# CNC-PowerSwitch-2016-v0_95.net
KiCad netlist of a schematic drawn in EAGLE
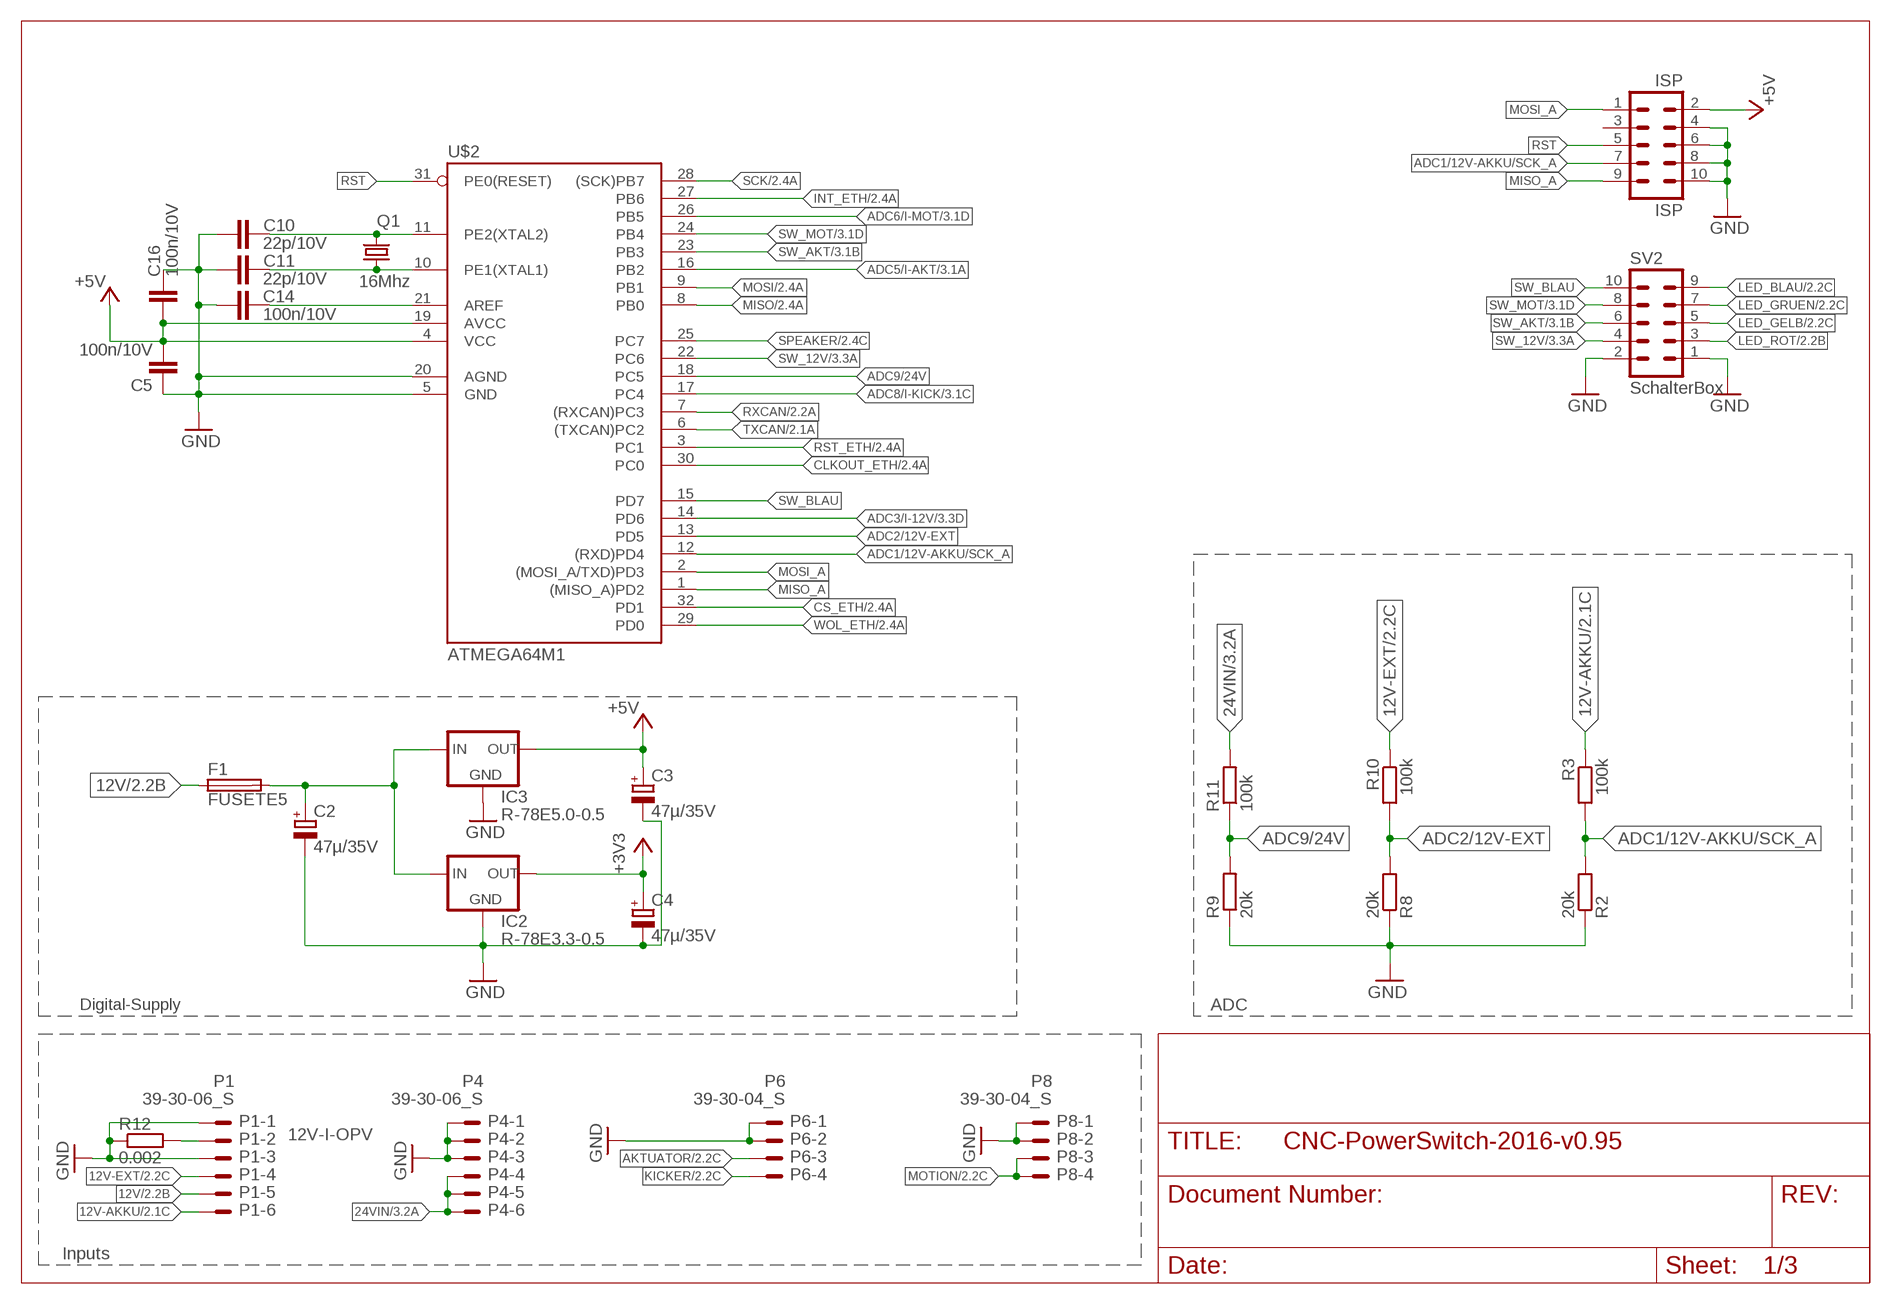
[diagram p0: schematic, sheet 1]
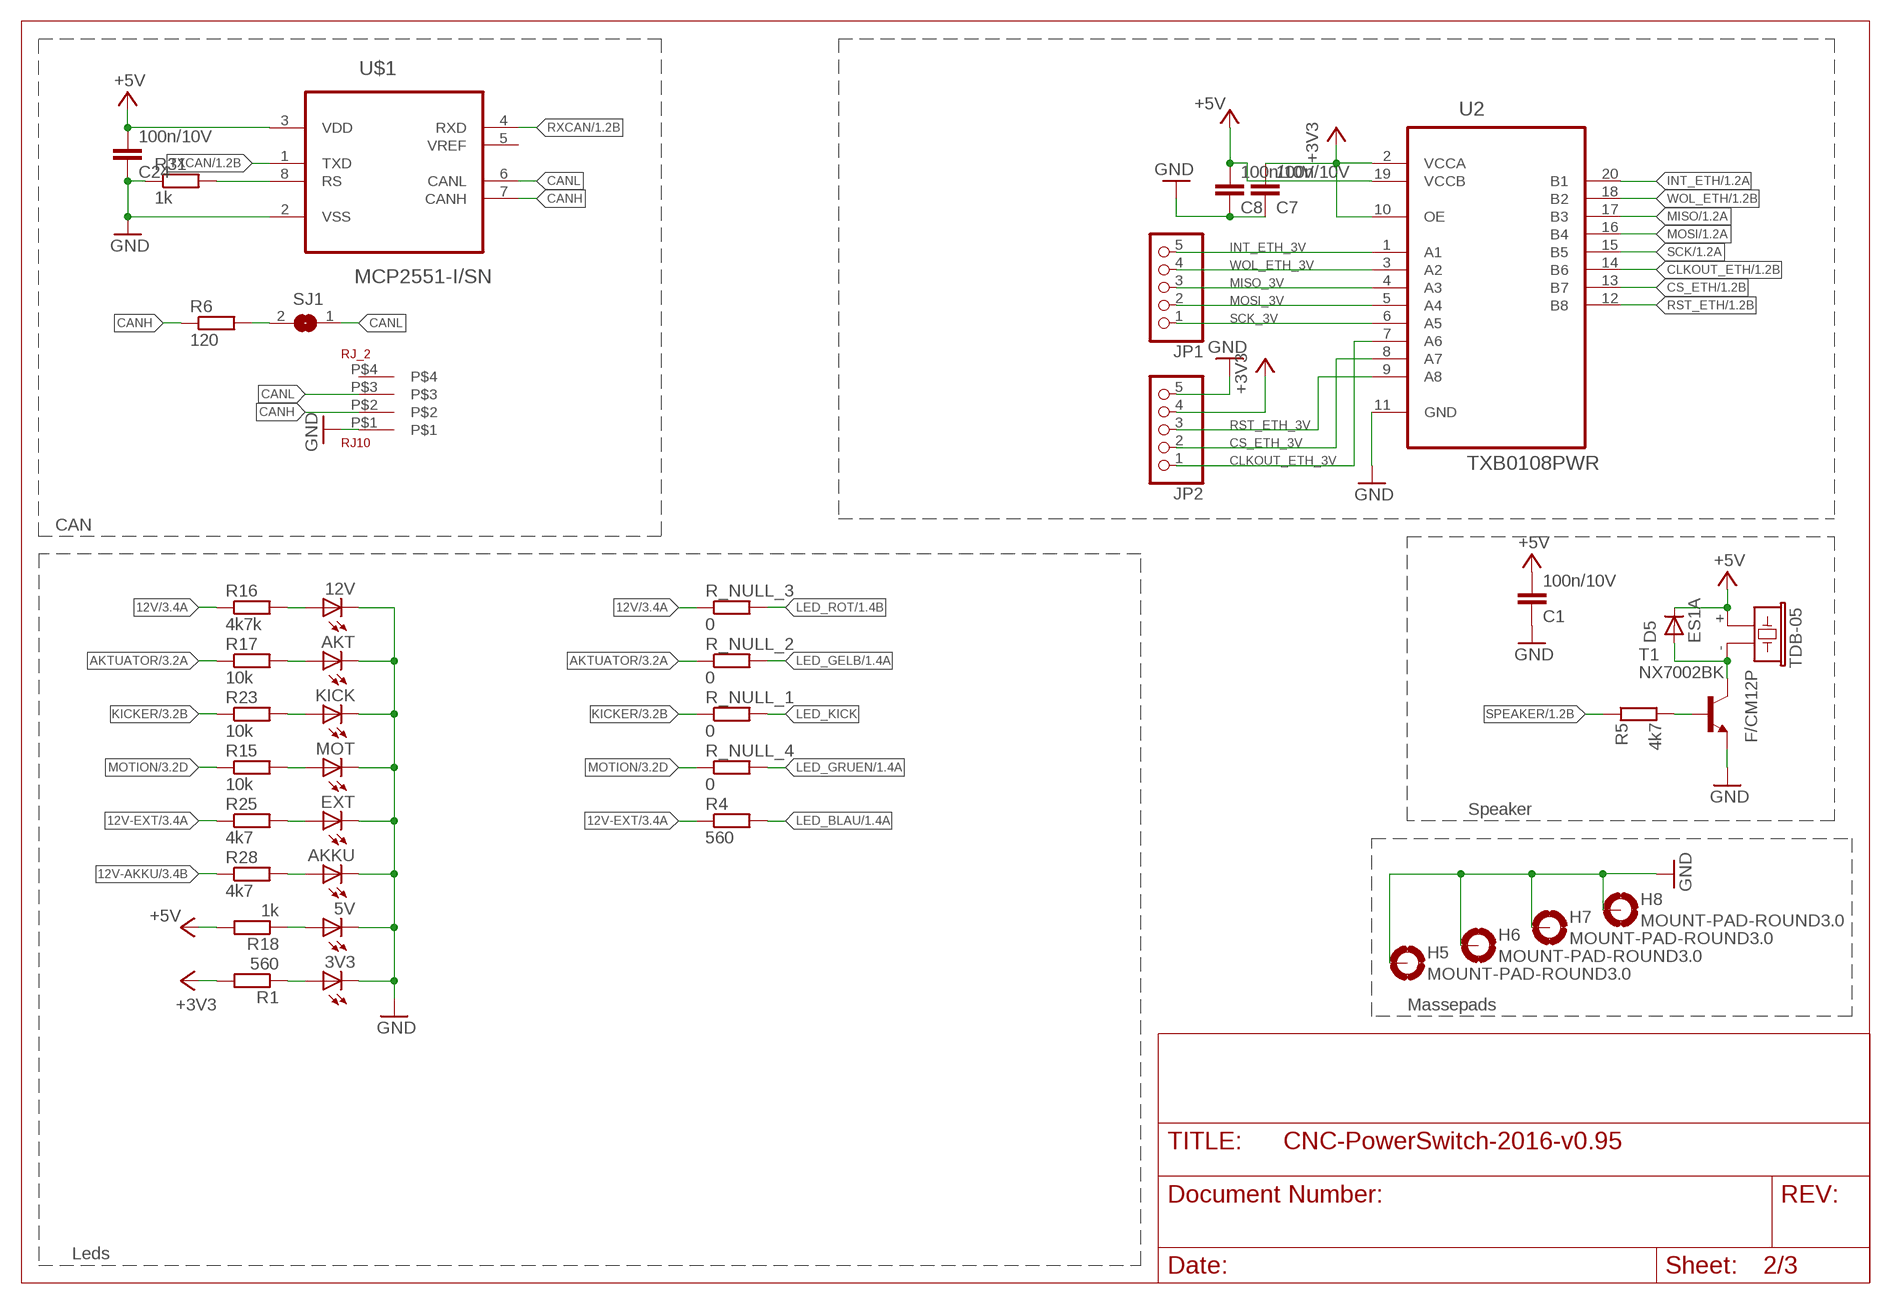
[diagram p1: schematic, sheet 2]
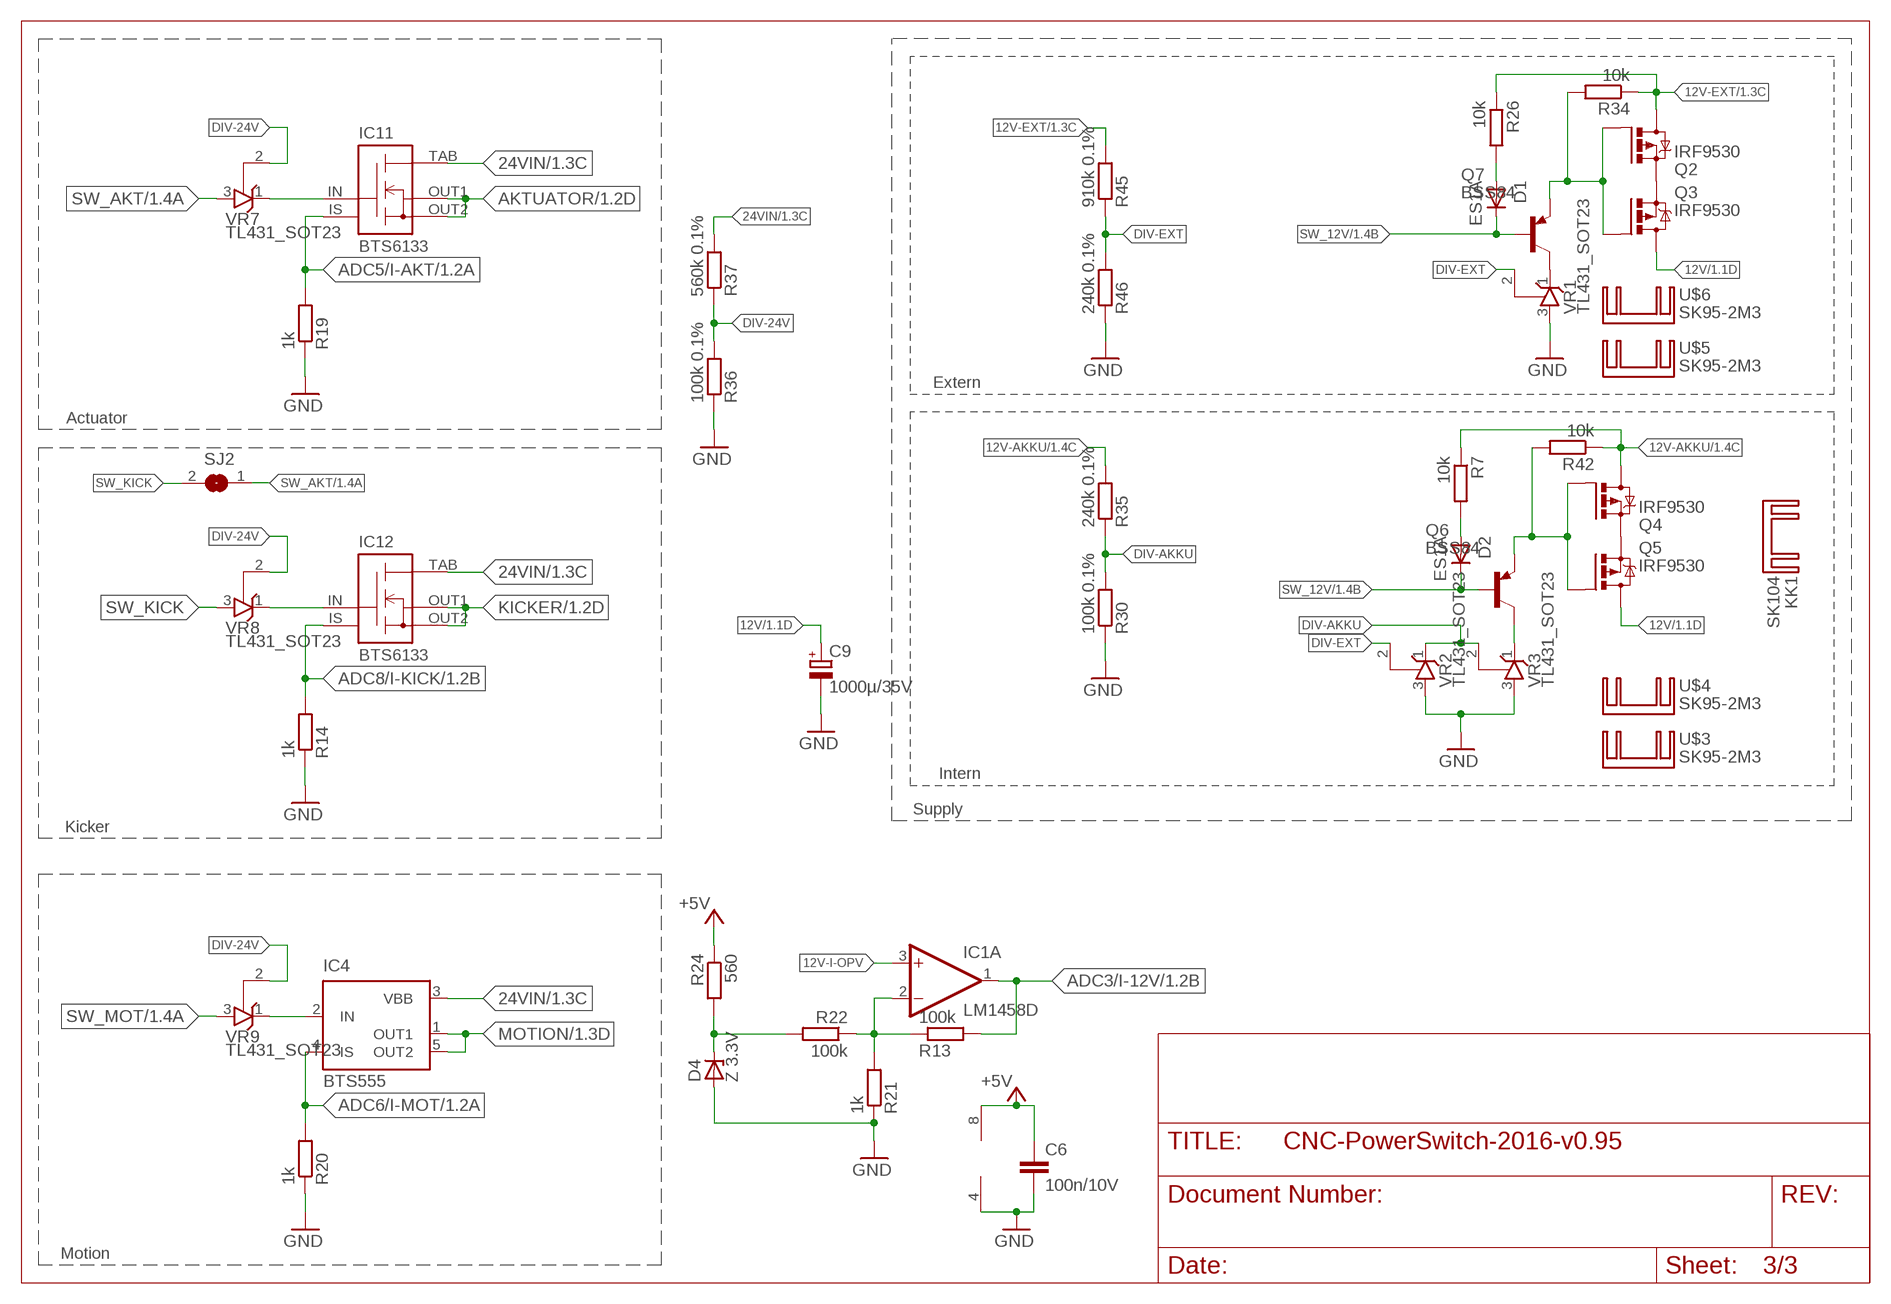
[diagram p2: schematic, sheet 3]

(export (version "E")
  (design (tool "Eeschema 10.0.6"))
  (components
    (comp (ref "C2")
      (value "47µ/35V")
      (footprint "eagle-import:PANASONIC_D")
      (libsource (lib "eagle-import") (part "CPOL-EUD"))
    )
    (comp (ref "C3")
      (value "47µ/35V")
      (footprint "eagle-import:PANASONIC_D")
      (libsource (lib "eagle-import") (part "CPOL-EUD"))
    )
    (comp (ref "C4")
      (value "47µ/35V")
      (footprint "eagle-import:PANASONIC_D")
      (libsource (lib "eagle-import") (part "CPOL-EUD"))
    )
    (comp (ref "C5")
      (value "100n/10V")
      (footprint "eagle-import:C0603")
      (libsource (lib "eagle-import") (part "C-EUC0603"))
    )
    (comp (ref "C10")
      (value "22p/10V")
      (footprint "eagle-import:C0603")
      (libsource (lib "eagle-import") (part "C-EUC0603"))
    )
    (comp (ref "C11")
      (value "22p/10V")
      (footprint "eagle-import:C0603")
      (libsource (lib "eagle-import") (part "C-EUC0603"))
    )
    (comp (ref "C14")
      (value "100n/10V")
      (footprint "eagle-import:C0603")
      (libsource (lib "eagle-import") (part "C-EUC0603"))
    )
    (comp (ref "C16")
      (value "100n/10V")
      (footprint "eagle-import:C0603")
      (libsource (lib "eagle-import") (part "C-EUC0603"))
    )
    (comp (ref "F1")
      (value "FUSETE5")
      (footprint "eagle-import:TE5")
      (libsource (lib "eagle-import") (part "FUSETE5"))
    )
    (comp (ref "IC2")
      (value "R-78E3.3-0.5")
      (footprint "eagle-import:SIP3")
      (fields (field (name "MF") "Recom") (field (name "MPN") "R-783.3-0.5"))
      (libsource (lib "eagle-import") (part "R-78E-0.53.3"))
    )
    (comp (ref "IC3")
      (value "R-78E5.0-0.5")
      (footprint "eagle-import:SIP3")
      (fields (field (name "MF") "Recom") (field (name "MPN") "R-785.0-0.5"))
      (libsource (lib "eagle-import") (part "R-78E-0.55.0"))
    )
    (comp (ref "ISP")
      (value "ISP")
      (footprint "eagle-import:ML10")
      (libsource (lib "eagle-import") (part "ML10"))
    )
    (comp (ref "P1")
      (value "39-30-06_S")
      (footprint "eagle-import:39-30-_06_")
      (libsource (lib "eagle-import") (part "39-30-?06?_S"))
    )
    (comp (ref "P4")
      (value "39-30-06_S")
      (footprint "eagle-import:39-30-_06_")
      (libsource (lib "eagle-import") (part "39-30-?06?_S"))
    )
    (comp (ref "P6")
      (value "39-30-04_S")
      (footprint "eagle-import:39-30-_04_")
      (libsource (lib "eagle-import") (part "39-30-?04?_S"))
    )
    (comp (ref "P8")
      (value "39-30-04_S")
      (footprint "eagle-import:39-30-_04_")
      (libsource (lib "eagle-import") (part "39-30-?04?_S"))
    )
    (comp (ref "Q1")
      (value "16Mhz")
      (footprint "eagle-import:HC49UP")
      (libsource (lib "eagle-import") (part "CRYSTALHC49UP"))
    )
    (comp (ref "R2")
      (value "20k")
      (footprint "eagle-import:R0805")
      (libsource (lib "eagle-import") (part "R-EU_R0805"))
    )
    (comp (ref "R3")
      (value "100k")
      (footprint "eagle-import:R0805")
      (libsource (lib "eagle-import") (part "R-EU_R0805"))
    )
    (comp (ref "R8")
      (value "20k")
      (footprint "eagle-import:R0805")
      (libsource (lib "eagle-import") (part "R-EU_R0805"))
    )
    (comp (ref "R9")
      (value "20k")
      (footprint "eagle-import:R0805")
      (libsource (lib "eagle-import") (part "R-EU_R0805"))
    )
    (comp (ref "R10")
      (value "100k")
      (footprint "eagle-import:R0805")
      (libsource (lib "eagle-import") (part "R-EU_R0805"))
    )
    (comp (ref "R11")
      (value "100k")
      (footprint "eagle-import:R0805")
      (libsource (lib "eagle-import") (part "R-EU_R0805"))
    )
    (comp (ref "R12")
      (value "0.002")
      (footprint "eagle-import:R2512")
      (libsource (lib "eagle-import") (part "R-EU_R2512"))
    )
    (comp (ref "SV2")
      (value "SchalterBox")
      (footprint "eagle-import:ML10L")
      (libsource (lib "eagle-import") (part "ML10L"))
    )
    (comp (ref "U$2")
      (value "ATMEGA64M1")
      (footprint "eagle-import:TQFP32-08")
      (libsource (lib "eagle-import") (part "ATMEGA64M1"))
    )
    (comp (ref "C6")
      (value "100n/10V")
      (footprint "eagle-import:C0603")
      (libsource (lib "eagle-import") (part "C-EUC0603"))
    )
    (comp (ref "C9")
      (value "1000µ/35V")
      (footprint "eagle-import:E5-10,5")
      (libsource (lib "eagle-import") (part "CPOL-EUE5-10.5"))
    )
    (comp (ref "D1")
      (value "ES1A")
      (footprint "eagle-import:SMA-DO214AC")
      (libsource (lib "eagle-import") (part "GF1"))
    )
    (comp (ref "D2")
      (value "ES1A")
      (footprint "eagle-import:SMA-DO214AC")
      (libsource (lib "eagle-import") (part "GF1"))
    )
    (comp (ref "D4")
      (value "Z 3.3V")
      (footprint "eagle-import:SOT23")
      (libsource (lib "eagle-import") (part "ZENER-DIODESOT23"))
    )
    (comp (ref "IC1")
      (value "LM1458D")
      (footprint "eagle-import:SO08")
      (libsource (lib "eagle-import") (part "1458DLM"))
    )
    (comp (ref "IC4")
      (value "BTS555")
      (footprint "eagle-import:TO220-51")
      (fields (field (name "MF") "FARNELL") (field (name "MPN") "BTS555."))
      (libsource (lib "eagle-import") (part "BTS555"))
    )
    (comp (ref "IC11")
      (value "BTS6133")
      (footprint "eagle-import:TO252-51")
      (libsource (lib "eagle-import") (part "BTS6133"))
    )
    (comp (ref "IC12")
      (value "BTS6133")
      (footprint "eagle-import:TO252-51")
      (libsource (lib "eagle-import") (part "BTS6133"))
    )
    (comp (ref "KK1")
      (value "SK104")
      (footprint "eagle-import:SK104")
      (libsource (lib "eagle-import") (part "SK104"))
    )
    (comp (ref "Q2")
      (value "IRF9530")
      (footprint "eagle-import:TO220BV")
      (libsource (lib "eagle-import") (part "IRF9530"))
    )
    (comp (ref "Q3")
      (value "IRF9530")
      (footprint "eagle-import:TO220BV")
      (libsource (lib "eagle-import") (part "IRF9530"))
    )
    (comp (ref "Q4")
      (value "IRF9530")
      (footprint "eagle-import:TO220BV")
      (libsource (lib "eagle-import") (part "IRF9530"))
    )
    (comp (ref "Q5")
      (value "IRF9530")
      (footprint "eagle-import:TO220BV")
      (libsource (lib "eagle-import") (part "IRF9530"))
    )
    (comp (ref "Q6")
      (value "BSS84")
      (footprint "eagle-import:SOT23-BEC")
      (libsource (lib "eagle-import") (part "BC858SMDALT1"))
    )
    (comp (ref "Q7")
      (value "BSS84")
      (footprint "eagle-import:SOT23-BEC")
      (libsource (lib "eagle-import") (part "BC858SMDALT1"))
    )
    (comp (ref "R7")
      (value "10k")
      (footprint "eagle-import:R0805")
      (libsource (lib "eagle-import") (part "R-EU_R0805"))
    )
    (comp (ref "R13")
      (value "100k")
      (footprint "eagle-import:R0805")
      (libsource (lib "eagle-import") (part "R-EU_R0805"))
    )
    (comp (ref "R14")
      (value "1k")
      (footprint "eagle-import:R0805")
      (libsource (lib "eagle-import") (part "R-EU_R0805"))
    )
    (comp (ref "R19")
      (value "1k")
      (footprint "eagle-import:R0805")
      (libsource (lib "eagle-import") (part "R-EU_R0805"))
    )
    (comp (ref "R20")
      (value "1k")
      (footprint "eagle-import:R0805")
      (libsource (lib "eagle-import") (part "R-EU_R0805"))
    )
    (comp (ref "R21")
      (value "1k")
      (footprint "eagle-import:R0805")
      (libsource (lib "eagle-import") (part "R-EU_R0805"))
    )
    (comp (ref "R22")
      (value "100k")
      (footprint "eagle-import:R0805")
      (libsource (lib "eagle-import") (part "R-EU_R0805"))
    )
    (comp (ref "R24")
      (value "560")
      (footprint "eagle-import:R0805")
      (libsource (lib "eagle-import") (part "R-EU_R0805"))
    )
    (comp (ref "R26")
      (value "10k")
      (footprint "eagle-import:R0805")
      (libsource (lib "eagle-import") (part "R-EU_R0805"))
    )
    (comp (ref "R30")
      (value "100k 0.1%")
      (footprint "eagle-import:R0805")
      (libsource (lib "eagle-import") (part "R-EU_R0805"))
    )
    (comp (ref "R34")
      (value "10k")
      (footprint "eagle-import:R0805")
      (libsource (lib "eagle-import") (part "R-EU_R0805"))
    )
    (comp (ref "R35")
      (value "240k 0.1%")
      (footprint "eagle-import:R0805")
      (libsource (lib "eagle-import") (part "R-EU_R0805"))
    )
    (comp (ref "R36")
      (value "100k 0.1%")
      (footprint "eagle-import:R0805")
      (libsource (lib "eagle-import") (part "R-EU_R0805"))
    )
    (comp (ref "R37")
      (value "560k 0.1%")
      (footprint "eagle-import:R0805")
      (libsource (lib "eagle-import") (part "R-EU_R0805"))
    )
    (comp (ref "R42")
      (value "10k")
      (footprint "eagle-import:R0805")
      (libsource (lib "eagle-import") (part "R-EU_R0805"))
    )
    (comp (ref "R45")
      (value "910k 0.1%")
      (footprint "eagle-import:R0805")
      (libsource (lib "eagle-import") (part "R-EU_R0805"))
    )
    (comp (ref "R46")
      (value "240k 0.1%")
      (footprint "eagle-import:R0805")
      (libsource (lib "eagle-import") (part "R-EU_R0805"))
    )
    (comp (ref "SJ2") (value "SJ") (footprint "eagle-import:SJ") (libsource (lib "eagle-import") (part "SJ")))
    (comp (ref "U$3")
      (value "SK95-2M3")
      (footprint "eagle-import:SK95-2M3")
      (libsource (lib "eagle-import") (part "SK95-2M3"))
    )
    (comp (ref "U$4")
      (value "SK95-2M3")
      (footprint "eagle-import:SK95-2M3")
      (libsource (lib "eagle-import") (part "SK95-2M3"))
    )
    (comp (ref "U$5")
      (value "SK95-2M3")
      (footprint "eagle-import:SK95-2M3")
      (libsource (lib "eagle-import") (part "SK95-2M3"))
    )
    (comp (ref "U$6")
      (value "SK95-2M3")
      (footprint "eagle-import:SK95-2M3")
      (libsource (lib "eagle-import") (part "SK95-2M3"))
    )
    (comp (ref "VR1")
      (value "TL431_SOT23")
      (footprint "eagle-import:SOT23")
      (libsource (lib "eagle-import") (part "TL431_SOT23"))
    )
    (comp (ref "VR2")
      (value "TL431_SOT23")
      (footprint "eagle-import:SOT23")
      (libsource (lib "eagle-import") (part "TL431_SOT23"))
    )
    (comp (ref "VR3")
      (value "TL431_SOT23")
      (footprint "eagle-import:SOT23")
      (libsource (lib "eagle-import") (part "TL431_SOT23"))
    )
    (comp (ref "VR7")
      (value "TL431_SOT23")
      (footprint "eagle-import:SOT23")
      (libsource (lib "eagle-import") (part "TL431_SOT23"))
    )
    (comp (ref "VR8")
      (value "TL431_SOT23")
      (footprint "eagle-import:SOT23")
      (libsource (lib "eagle-import") (part "TL431_SOT23"))
    )
    (comp (ref "VR9")
      (value "TL431_SOT23")
      (footprint "eagle-import:SOT23")
      (libsource (lib "eagle-import") (part "TL431_SOT23"))
    )
    (comp (ref "3V3")
      (value "LEDCHIPLED_0805")
      (footprint "eagle-import:CHIPLED_0805")
      (libsource (lib "eagle-import") (part "LEDCHIPLED_0805"))
    )
    (comp (ref "5V")
      (value "LEDCHIPLED_0805")
      (footprint "eagle-import:CHIPLED_0805")
      (libsource (lib "eagle-import") (part "LEDCHIPLED_0805"))
    )
    (comp (ref "12V")
      (value "LEDCHIPLED_0805")
      (footprint "eagle-import:CHIPLED_0805")
      (libsource (lib "eagle-import") (part "LEDCHIPLED_0805"))
    )
    (comp (ref "AKKU")
      (value "LEDCHIPLED_0805")
      (footprint "eagle-import:CHIPLED_0805")
      (libsource (lib "eagle-import") (part "LEDCHIPLED_0805"))
    )
    (comp (ref "AKT")
      (value "LEDCHIPLED_0805")
      (footprint "eagle-import:CHIPLED_0805")
      (libsource (lib "eagle-import") (part "LEDCHIPLED_0805"))
    )
    (comp (ref "C1")
      (value "100n/10V")
      (footprint "eagle-import:C0603")
      (libsource (lib "eagle-import") (part "C-EUC0603"))
    )
    (comp (ref "C7")
      (value "100n/10V")
      (footprint "eagle-import:C0603")
      (libsource (lib "eagle-import") (part "C-EUC0603"))
    )
    (comp (ref "C8")
      (value "100n/10V")
      (footprint "eagle-import:C0603")
      (libsource (lib "eagle-import") (part "C-EUC0603"))
    )
    (comp (ref "C24")
      (value "100n/10V")
      (footprint "eagle-import:C0603")
      (libsource (lib "eagle-import") (part "C-EUC0603"))
    )
    (comp (ref "D5")
      (value "ES1A")
      (footprint "eagle-import:SMA-DO214AC")
      (libsource (lib "eagle-import") (part "GF1"))
    )
    (comp (ref "EXT")
      (value "LEDCHIPLED_0805")
      (footprint "eagle-import:CHIPLED_0805")
      (libsource (lib "eagle-import") (part "LEDCHIPLED_0805"))
    )
    (comp (ref "H5")
      (value "MOUNT-PAD-ROUND3.0")
      (footprint "eagle-import:3,0-PAD")
      (libsource (lib "eagle-import") (part "MOUNT-PAD-ROUND3.0"))
    )
    (comp (ref "H6")
      (value "MOUNT-PAD-ROUND3.0")
      (footprint "eagle-import:3,0-PAD")
      (libsource (lib "eagle-import") (part "MOUNT-PAD-ROUND3.0"))
    )
    (comp (ref "H7")
      (value "MOUNT-PAD-ROUND3.0")
      (footprint "eagle-import:3,0-PAD")
      (libsource (lib "eagle-import") (part "MOUNT-PAD-ROUND3.0"))
    )
    (comp (ref "H8")
      (value "MOUNT-PAD-ROUND3.0")
      (footprint "eagle-import:3,0-PAD")
      (libsource (lib "eagle-import") (part "MOUNT-PAD-ROUND3.0"))
    )
    (comp (ref "JP1")
      (value "PINHD-1X5")
      (footprint "eagle-import:1X05")
      (libsource (lib "eagle-import") (part "PINHD-1X5"))
    )
    (comp (ref "JP2")
      (value "PINHD-1X5")
      (footprint "eagle-import:1X05")
      (libsource (lib "eagle-import") (part "PINHD-1X5"))
    )
    (comp (ref "KICK")
      (value "LEDCHIPLED_0805")
      (footprint "eagle-import:CHIPLED_0805")
      (libsource (lib "eagle-import") (part "LEDCHIPLED_0805"))
    )
    (comp (ref "MOT")
      (value "LEDCHIPLED_0805")
      (footprint "eagle-import:CHIPLED_0805")
      (libsource (lib "eagle-import") (part "LEDCHIPLED_0805"))
    )
    (comp (ref "R1")
      (value "560")
      (footprint "eagle-import:R0805")
      (libsource (lib "eagle-import") (part "R-EU_R0805"))
    )
    (comp (ref "R4")
      (value "560")
      (footprint "eagle-import:R0805")
      (libsource (lib "eagle-import") (part "R-EU_R0805"))
    )
    (comp (ref "R5")
      (value "4k7")
      (footprint "eagle-import:R0805")
      (libsource (lib "eagle-import") (part "R-EU_R0805"))
    )
    (comp (ref "R6")
      (value "120")
      (footprint "eagle-import:M0805")
      (libsource (lib "eagle-import") (part "R-EU_M0805"))
    )
    (comp (ref "R15")
      (value "10k")
      (footprint "eagle-import:R0805")
      (libsource (lib "eagle-import") (part "R-EU_R0805"))
    )
    (comp (ref "R16")
      (value "4k7k")
      (footprint "eagle-import:R0805")
      (libsource (lib "eagle-import") (part "R-EU_R0805"))
    )
    (comp (ref "R17")
      (value "10k")
      (footprint "eagle-import:R0805")
      (libsource (lib "eagle-import") (part "R-EU_R0805"))
    )
    (comp (ref "R18")
      (value "1k")
      (footprint "eagle-import:R0805")
      (libsource (lib "eagle-import") (part "R-EU_R0805"))
    )
    (comp (ref "R23")
      (value "10k")
      (footprint "eagle-import:R0805")
      (libsource (lib "eagle-import") (part "R-EU_R0805"))
    )
    (comp (ref "R25")
      (value "4k7")
      (footprint "eagle-import:R0805")
      (libsource (lib "eagle-import") (part "R-EU_R0805"))
    )
    (comp (ref "R28")
      (value "4k7")
      (footprint "eagle-import:R0805")
      (libsource (lib "eagle-import") (part "R-EU_R0805"))
    )
    (comp (ref "R31")
      (value "1k")
      (footprint "eagle-import:R0805")
      (libsource (lib "eagle-import") (part "R-EU_R0805"))
    )
    (comp (ref "RJ_2")
      (value "RJ10")
      (footprint "eagle-import:RJ10")
      (libsource (lib "eagle-import") (part "RJ10"))
    )
    (comp (ref "R_NULL_1")
      (value "0")
      (footprint "eagle-import:R0402")
      (libsource (lib "eagle-import") (part "R-EU_R0402"))
    )
    (comp (ref "R_NULL_2")
      (value "0")
      (footprint "eagle-import:R0402")
      (libsource (lib "eagle-import") (part "R-EU_R0402"))
    )
    (comp (ref "R_NULL_3")
      (value "0")
      (footprint "eagle-import:R0402")
      (libsource (lib "eagle-import") (part "R-EU_R0402"))
    )
    (comp (ref "R_NULL_4")
      (value "0")
      (footprint "eagle-import:R0402")
      (libsource (lib "eagle-import") (part "R-EU_R0402"))
    )
    (comp (ref "SJ1") (value "SJ") (footprint "eagle-import:SJ") (libsource (lib "eagle-import") (part "SJ")))
    (comp (ref "T1")
      (value "NX7002BK")
      (footprint "eagle-import:SOT23")
      (libsource (lib "eagle-import") (part "BC849"))
    )
    (comp (ref "TDB-05")
      (value "F/CM12P")
      (footprint "eagle-import:F_CM12P")
      (libsource (lib "eagle-import") (part "F/CM12P"))
    )
    (comp (ref "U$1")
      (value "MCP2551-I/SN")
      (footprint "eagle-import:SOIC127P600X175-8N")
      (libsource (lib "eagle-import") (part "MCP2551-I/SN"))
    )
    (comp (ref "U2")
      (value "TXB0108PWR")
      (footprint "eagle-import:SOP65P640X120-20N")
      (libsource (lib "eagle-import") (part "TXB0108PWR"))
    )
  )
  (nets
    (net (code "1") (name "+3V3") (class "Default")
      (node (ref "C4") (pin "+") (pinfunction "+_+") (pintype "passive"))
      (node (ref "C7") (pin "2") (pinfunction "2_2") (pintype "passive"))
      (node (ref "IC2") (pin "3") (pinfunction "OUT_3") (pintype "passive"))
      (node (ref "JP2") (pin "4") (pinfunction "4_4") (pintype "passive"))
      (node (ref "R1") (pin "2") (pinfunction "2_2") (pintype "passive"))
      (node (ref "U2") (pin "10") (pinfunction "OE_10") (pintype "input"))
      (node (ref "U2") (pin "2") (pinfunction "VCCA_2") (pintype "power_in"))
    )
    (net (code "2") (name "+5V") (class "Default")
      (node (ref "C1") (pin "2") (pinfunction "2_2") (pintype "passive"))
      (node (ref "C16") (pin "1") (pinfunction "1_1") (pintype "passive"))
      (node (ref "C24") (pin "2") (pinfunction "2_2") (pintype "passive"))
      (node (ref "C3") (pin "+") (pinfunction "+_+") (pintype "passive"))
      (node (ref "C5") (pin "2") (pinfunction "2_2") (pintype "passive"))
      (node (ref "C6") (pin "1") (pinfunction "1_1") (pintype "passive"))
      (node (ref "C8") (pin "2") (pinfunction "2_2") (pintype "passive"))
      (node (ref "D5") (pin "K") (pinfunction "C_K") (pintype "passive"))
      (node (ref "IC1") (pin "8") (pinfunction "V+_8") (pintype "power_in"))
      (node (ref "IC3") (pin "3") (pinfunction "OUT_3") (pintype "passive"))
      (node (ref "ISP") (pin "2") (pinfunction "2_2") (pintype "passive"))
      (node (ref "R18") (pin "2") (pinfunction "2_2") (pintype "passive"))
      (node (ref "R24") (pin "1") (pinfunction "1_1") (pintype "passive"))
      (node (ref "TDB-05") (pin "+") (pinfunction "1_+") (pintype "passive"))
      (node (ref "U$1") (pin "3") (pinfunction "VDD_3") (pintype "power_in"))
      (node (ref "U$2") (pin "19") (pinfunction "AVCC_19") (pintype "bidirectional"))
      (node (ref "U$2") (pin "4") (pinfunction "VCC_4") (pintype "bidirectional"))
      (node (ref "U2") (pin "19") (pinfunction "VCCB_19") (pintype "power_in"))
    )
    (net (code "3") (name "12V") (class "Default")
      (node (ref "C9") (pin "+") (pinfunction "+_+") (pintype "passive"))
      (node (ref "F1") (pin "1") (pinfunction "1_1") (pintype "passive"))
      (node (ref "P1") (pin "5") (pinfunction "P_5") (pintype "passive"))
      (node (ref "Q3") (pin "D") (pinfunction "D_D") (pintype "passive"))
      (node (ref "Q5") (pin "D") (pinfunction "D_D") (pintype "passive"))
      (node (ref "R16") (pin "1") (pinfunction "1_1") (pintype "passive"))
      (node (ref "R_NULL_3") (pin "1") (pinfunction "1_1") (pintype "passive"))
    )
    (net (code "4") (name "12V-AKKU") (class "Default")
      (node (ref "P1") (pin "6") (pinfunction "P_6") (pintype "passive"))
      (node (ref "Q4") (pin "D") (pinfunction "D_D") (pintype "passive"))
      (node (ref "R28") (pin "1") (pinfunction "1_1") (pintype "passive"))
      (node (ref "R3") (pin "1") (pinfunction "1_1") (pintype "passive"))
      (node (ref "R35") (pin "2") (pinfunction "2_2") (pintype "passive"))
      (node (ref "R42") (pin "1") (pinfunction "1_1") (pintype "passive"))
      (node (ref "R7") (pin "1") (pinfunction "1_1") (pintype "passive"))
    )
    (net (code "5") (name "12V-EXT") (class "Default")
      (node (ref "P1") (pin "4") (pinfunction "P_4") (pintype "passive"))
      (node (ref "Q2") (pin "D") (pinfunction "D_D") (pintype "passive"))
      (node (ref "R10") (pin "1") (pinfunction "1_1") (pintype "passive"))
      (node (ref "R25") (pin "1") (pinfunction "1_1") (pintype "passive"))
      (node (ref "R26") (pin "1") (pinfunction "1_1") (pintype "passive"))
      (node (ref "R34") (pin "1") (pinfunction "1_1") (pintype "passive"))
      (node (ref "R4") (pin "1") (pinfunction "1_1") (pintype "passive"))
      (node (ref "R45") (pin "2") (pinfunction "2_2") (pintype "passive"))
    )
    (net (code "6") (name "12V-I-OPV") (class "Default")
      (node (ref "IC1") (pin "3") (pinfunction "+IN_3") (pintype "input"))
      (node (ref "P1") (pin "2") (pinfunction "P_2") (pintype "passive"))
      (node (ref "R12") (pin "2") (pinfunction "2_2") (pintype "passive"))
    )
    (net (code "7") (name "24VIN") (class "Default")
      (node (ref "IC11") (pin "TAB") (pinfunction "VBB_TAB") (pintype "power_in"))
      (node (ref "IC12") (pin "TAB") (pinfunction "VBB_TAB") (pintype "power_in"))
      (node (ref "IC4") (pin "3") (pinfunction "VBB_3") (pintype "passive"))
      (node (ref "P4") (pin "4") (pinfunction "P_4") (pintype "passive"))
      (node (ref "P4") (pin "5") (pinfunction "P_5") (pintype "passive"))
      (node (ref "P4") (pin "6") (pinfunction "P_6") (pintype "passive"))
      (node (ref "R11") (pin "2") (pinfunction "2_2") (pintype "passive"))
      (node (ref "R37") (pin "2") (pinfunction "2_2") (pintype "passive"))
    )
    (net (code "8") (name "ADC1{slash}12V-AKKU{slash}SCK_A") (class "Default")
      (node (ref "ISP") (pin "7") (pinfunction "7_7") (pintype "passive"))
      (node (ref "R2") (pin "2") (pinfunction "2_2") (pintype "passive"))
      (node (ref "R3") (pin "2") (pinfunction "2_2") (pintype "passive"))
      (node (ref "U$2") (pin "12") (pinfunction "(RXD)PD4_12") (pintype "bidirectional"))
    )
    (net (code "9") (name "ADC2{slash}12V-EXT") (class "Default")
      (node (ref "R10") (pin "2") (pinfunction "2_2") (pintype "passive"))
      (node (ref "R8") (pin "2") (pinfunction "2_2") (pintype "passive"))
      (node (ref "U$2") (pin "13") (pinfunction "PD5_13") (pintype "bidirectional"))
    )
    (net (code "10") (name "ADC3{slash}I-12V") (class "Default")
      (node (ref "IC1") (pin "1") (pinfunction "OUT_1") (pintype "output"))
      (node (ref "R13") (pin "2") (pinfunction "2_2") (pintype "passive"))
      (node (ref "U$2") (pin "14") (pinfunction "PD6_14") (pintype "bidirectional"))
    )
    (net (code "11") (name "ADC5{slash}I-AKT") (class "Default")
      (node (ref "IC11") (pin "IS") (pinfunction "IS_IS") (pintype "passive"))
      (node (ref "R19") (pin "2") (pinfunction "2_2") (pintype "passive"))
      (node (ref "U$2") (pin "16") (pinfunction "PB2_16") (pintype "bidirectional"))
    )
    (net (code "12") (name "ADC6{slash}I-MOT") (class "Default")
      (node (ref "IC4") (pin "4") (pinfunction "IS_4") (pintype "passive"))
      (node (ref "R20") (pin "2") (pinfunction "2_2") (pintype "passive"))
      (node (ref "U$2") (pin "26") (pinfunction "PB5_26") (pintype "bidirectional"))
    )
    (net (code "13") (name "ADC8{slash}I-KICK") (class "Default")
      (node (ref "IC12") (pin "IS") (pinfunction "IS_IS") (pintype "passive"))
      (node (ref "R14") (pin "2") (pinfunction "2_2") (pintype "passive"))
      (node (ref "U$2") (pin "17") (pinfunction "PC4_17") (pintype "bidirectional"))
    )
    (net (code "14") (name "ADC9{slash}24V") (class "Default")
      (node (ref "R11") (pin "1") (pinfunction "1_1") (pintype "passive"))
      (node (ref "R9") (pin "2") (pinfunction "2_2") (pintype "passive"))
      (node (ref "U$2") (pin "18") (pinfunction "PC5_18") (pintype "bidirectional"))
    )
    (net (code "15") (name "AKTUATOR") (class "Default")
      (node (ref "IC11") (pin "OUT1") (pinfunction "OUT_OUT1") (pintype "passive"))
      (node (ref "IC11") (pin "OUT2") (pinfunction "OUT_OUT2") (pintype "passive"))
      (node (ref "P6") (pin "3") (pinfunction "P_3") (pintype "passive"))
      (node (ref "R17") (pin "1") (pinfunction "1_1") (pintype "passive"))
      (node (ref "R_NULL_2") (pin "1") (pinfunction "1_1") (pintype "passive"))
    )
    (net (code "16") (name "CANH") (class "Default")
      (node (ref "R6") (pin "1") (pinfunction "1_1") (pintype "passive"))
      (node (ref "RJ_2") (pin "P$2") (pinfunction "P$2_P$2") (pintype "bidirectional"))
      (node (ref "U$1") (pin "7") (pinfunction "CANH_7") (pintype "bidirectional"))
    )
    (net (code "17") (name "CANL") (class "Default")
      (node (ref "RJ_2") (pin "P$3") (pinfunction "P$3_P$3") (pintype "bidirectional"))
      (node (ref "SJ1") (pin "1") (pinfunction "1_1") (pintype "passive"))
      (node (ref "U$1") (pin "6") (pinfunction "CANL_6") (pintype "bidirectional"))
    )
    (net (code "18") (name "CLKOUT_ETH") (class "Default")
      (node (ref "U$2") (pin "30") (pinfunction "PC0_30") (pintype "bidirectional"))
      (node (ref "U2") (pin "14") (pinfunction "B6_14") (pintype "bidirectional"))
    )
    (net (code "19") (name "CLKOUT_ETH_3V") (class "Default")
      (node (ref "JP2") (pin "1") (pinfunction "1_1") (pintype "passive"))
      (node (ref "U2") (pin "7") (pinfunction "A6_7") (pintype "bidirectional"))
    )
    (net (code "20") (name "CS_ETH") (class "Default")
      (node (ref "U$2") (pin "32") (pinfunction "PD1_32") (pintype "bidirectional"))
      (node (ref "U2") (pin "13") (pinfunction "B7_13") (pintype "bidirectional"))
    )
    (net (code "21") (name "CS_ETH_3V") (class "Default")
      (node (ref "JP2") (pin "2") (pinfunction "2_2") (pintype "passive"))
      (node (ref "U2") (pin "8") (pinfunction "A7_8") (pintype "bidirectional"))
    )
    (net (code "22") (name "DIV-24V") (class "Default")
      (node (ref "R36") (pin "2") (pinfunction "2_2") (pintype "passive"))
      (node (ref "R37") (pin "1") (pinfunction "1_1") (pintype "passive"))
      (node (ref "VR7") (pin "2") (pinfunction "R_2") (pintype "passive"))
      (node (ref "VR8") (pin "2") (pinfunction "R_2") (pintype "passive"))
      (node (ref "VR9") (pin "2") (pinfunction "R_2") (pintype "passive"))
    )
    (net (code "23") (name "DIV-AKKU") (class "Default")
      (node (ref "R30") (pin "2") (pinfunction "2_2") (pintype "passive"))
      (node (ref "R35") (pin "1") (pinfunction "1_1") (pintype "passive"))
      (node (ref "VR2") (pin "1") (pinfunction "C_1") (pintype "passive"))
      (node (ref "VR3") (pin "2") (pinfunction "R_2") (pintype "passive"))
    )
    (net (code "24") (name "DIV-EXT") (class "Default")
      (node (ref "R45") (pin "1") (pinfunction "1_1") (pintype "passive"))
      (node (ref "R46") (pin "2") (pinfunction "2_2") (pintype "passive"))
      (node (ref "VR1") (pin "2") (pinfunction "R_2") (pintype "passive"))
      (node (ref "VR2") (pin "2") (pinfunction "R_2") (pintype "passive"))
    )
    (net (code "25") (name "GND") (class "Default")
      (node (ref "12V") (pin "C") (pinfunction "C_C") (pintype "passive"))
      (node (ref "3V3") (pin "C") (pinfunction "C_C") (pintype "passive"))
      (node (ref "5V") (pin "C") (pinfunction "C_C") (pintype "passive"))
      (node (ref "AKKU") (pin "C") (pinfunction "C_C") (pintype "passive"))
      (node (ref "AKT") (pin "C") (pinfunction "C_C") (pintype "passive"))
      (node (ref "C1") (pin "1") (pinfunction "1_1") (pintype "passive"))
      (node (ref "C10") (pin "1") (pinfunction "1_1") (pintype "passive"))
      (node (ref "C11") (pin "1") (pinfunction "1_1") (pintype "passive"))
      (node (ref "C14") (pin "1") (pinfunction "1_1") (pintype "passive"))
      (node (ref "C16") (pin "2") (pinfunction "2_2") (pintype "passive"))
      (node (ref "C2") (pin "-") (pinfunction "-_-") (pintype "passive"))
      (node (ref "C24") (pin "1") (pinfunction "1_1") (pintype "passive"))
      (node (ref "C3") (pin "-") (pinfunction "-_-") (pintype "passive"))
      (node (ref "C4") (pin "-") (pinfunction "-_-") (pintype "passive"))
      (node (ref "C5") (pin "1") (pinfunction "1_1") (pintype "passive"))
      (node (ref "C6") (pin "2") (pinfunction "2_2") (pintype "passive"))
      (node (ref "C7") (pin "1") (pinfunction "1_1") (pintype "passive"))
      (node (ref "C8") (pin "1") (pinfunction "1_1") (pintype "passive"))
      (node (ref "C9") (pin "-") (pinfunction "-_-") (pintype "passive"))
      (node (ref "D4") (pin "1") (pinfunction "A_1") (pintype "passive"))
      (node (ref "EXT") (pin "C") (pinfunction "C_C") (pintype "passive"))
      (node (ref "H5") (pin "B3,0") (pinfunction "MOUNT_B3,0") (pintype "passive"))
      (node (ref "H6") (pin "B3,0") (pinfunction "MOUNT_B3,0") (pintype "passive"))
      (node (ref "H7") (pin "B3,0") (pinfunction "MOUNT_B3,0") (pintype "passive"))
      (node (ref "H8") (pin "B3,0") (pinfunction "MOUNT_B3,0") (pintype "passive"))
      (node (ref "IC1") (pin "4") (pinfunction "V-_4") (pintype "power_in"))
      (node (ref "IC2") (pin "2") (pinfunction "GND_2") (pintype "input"))
      (node (ref "IC3") (pin "2") (pinfunction "GND_2") (pintype "input"))
      (node (ref "ISP") (pin "10") (pinfunction "10_10") (pintype "passive"))
      (node (ref "ISP") (pin "4") (pinfunction "4_4") (pintype "passive"))
      (node (ref "ISP") (pin "6") (pinfunction "6_6") (pintype "passive"))
      (node (ref "ISP") (pin "8") (pinfunction "8_8") (pintype "passive"))
      (node (ref "JP2") (pin "5") (pinfunction "5_5") (pintype "passive"))
      (node (ref "KICK") (pin "C") (pinfunction "C_C") (pintype "passive"))
      (node (ref "MOT") (pin "C") (pinfunction "C_C") (pintype "passive"))
      (node (ref "P1") (pin "1") (pinfunction "P_1") (pintype "passive"))
      (node (ref "P1") (pin "3") (pinfunction "P_3") (pintype "passive"))
      (node (ref "P4") (pin "1") (pinfunction "P_1") (pintype "passive"))
      (node (ref "P4") (pin "2") (pinfunction "P_2") (pintype "passive"))
      (node (ref "P4") (pin "3") (pinfunction "P_3") (pintype "passive"))
      (node (ref "P6") (pin "1") (pinfunction "P_1") (pintype "passive"))
      (node (ref "P6") (pin "2") (pinfunction "P_2") (pintype "passive"))
      (node (ref "P8") (pin "1") (pinfunction "P_1") (pintype "passive"))
      (node (ref "P8") (pin "2") (pinfunction "P_2") (pintype "passive"))
      (node (ref "R12") (pin "1") (pinfunction "1_1") (pintype "passive"))
      (node (ref "R14") (pin "1") (pinfunction "1_1") (pintype "passive"))
      (node (ref "R19") (pin "1") (pinfunction "1_1") (pintype "passive"))
      (node (ref "R2") (pin "1") (pinfunction "1_1") (pintype "passive"))
      (node (ref "R20") (pin "1") (pinfunction "1_1") (pintype "passive"))
      (node (ref "R21") (pin "1") (pinfunction "1_1") (pintype "passive"))
      (node (ref "R30") (pin "1") (pinfunction "1_1") (pintype "passive"))
      (node (ref "R31") (pin "1") (pinfunction "1_1") (pintype "passive"))
      (node (ref "R36") (pin "1") (pinfunction "1_1") (pintype "passive"))
      (node (ref "R46") (pin "1") (pinfunction "1_1") (pintype "passive"))
      (node (ref "R8") (pin "1") (pinfunction "1_1") (pintype "passive"))
      (node (ref "R9") (pin "1") (pinfunction "1_1") (pintype "passive"))
      (node (ref "RJ_2") (pin "P$1") (pinfunction "P$1_P$1") (pintype "bidirectional"))
      (node (ref "SV2") (pin "1") (pinfunction "1_1") (pintype "passive"))
      (node (ref "SV2") (pin "2") (pinfunction "2_2") (pintype "passive"))
      (node (ref "T1") (pin "2") (pinfunction "E_2") (pintype "passive"))
      (node (ref "U$1") (pin "2") (pinfunction "VSS_2") (pintype "passive"))
      (node (ref "U$2") (pin "20") (pinfunction "AGND_20") (pintype "power_in"))
      (node (ref "U$2") (pin "5") (pinfunction "GND_5") (pintype "power_in"))
      (node (ref "U2") (pin "11") (pinfunction "GND_11") (pintype "passive"))
      (node (ref "VR1") (pin "3") (pinfunction "A_3") (pintype "passive"))
      (node (ref "VR2") (pin "3") (pinfunction "A_3") (pintype "passive"))
      (node (ref "VR3") (pin "3") (pinfunction "A_3") (pintype "passive"))
    )
    (net (code "26") (name "INT_ETH") (class "Default")
      (node (ref "U$2") (pin "27") (pinfunction "PB6_27") (pintype "bidirectional"))
      (node (ref "U2") (pin "20") (pinfunction "B1_20") (pintype "bidirectional"))
    )
    (net (code "27") (name "INT_ETH_3V") (class "Default")
      (node (ref "JP1") (pin "5") (pinfunction "5_5") (pintype "passive"))
      (node (ref "U2") (pin "1") (pinfunction "A1_1") (pintype "bidirectional"))
    )
    (net (code "28") (name "KICKER") (class "Default")
      (node (ref "IC12") (pin "OUT1") (pinfunction "OUT_OUT1") (pintype "passive"))
      (node (ref "IC12") (pin "OUT2") (pinfunction "OUT_OUT2") (pintype "passive"))
      (node (ref "P6") (pin "4") (pinfunction "P_4") (pintype "passive"))
      (node (ref "R23") (pin "1") (pinfunction "1_1") (pintype "passive"))
      (node (ref "R_NULL_1") (pin "1") (pinfunction "1_1") (pintype "passive"))
    )
    (net (code "29") (name "LED_BLAU") (class "Default")
      (node (ref "R4") (pin "2") (pinfunction "2_2") (pintype "passive"))
      (node (ref "SV2") (pin "9") (pinfunction "9_9") (pintype "passive"))
    )
    (net (code "30") (name "LED_GELB") (class "Default")
      (node (ref "R_NULL_2") (pin "2") (pinfunction "2_2") (pintype "passive"))
      (node (ref "SV2") (pin "5") (pinfunction "5_5") (pintype "passive"))
    )
    (net (code "31") (name "LED_GRUEN") (class "Default")
      (node (ref "R_NULL_4") (pin "2") (pinfunction "2_2") (pintype "passive"))
      (node (ref "SV2") (pin "7") (pinfunction "7_7") (pintype "passive"))
    )
    (net (code "32") (name "LED_KICK") (class "Default")
      (node (ref "R_NULL_1") (pin "2") (pinfunction "2_2") (pintype "passive"))
    )
    (net (code "33") (name "LED_ROT") (class "Default")
      (node (ref "R_NULL_3") (pin "2") (pinfunction "2_2") (pintype "passive"))
      (node (ref "SV2") (pin "3") (pinfunction "3_3") (pintype "passive"))
    )
    (net (code "34") (name "MISO") (class "Default")
      (node (ref "U$2") (pin "8") (pinfunction "PB0_8") (pintype "bidirectional"))
      (node (ref "U2") (pin "17") (pinfunction "B3_17") (pintype "bidirectional"))
    )
    (net (code "35") (name "MISO_3V") (class "Default")
      (node (ref "JP1") (pin "3") (pinfunction "3_3") (pintype "passive"))
      (node (ref "U2") (pin "4") (pinfunction "A3_4") (pintype "bidirectional"))
    )
    (net (code "36") (name "MISO_A") (class "Default")
      (node (ref "ISP") (pin "9") (pinfunction "9_9") (pintype "passive"))
      (node (ref "U$2") (pin "1") (pinfunction "(MISO_A)PD2_1") (pintype "bidirectional"))
    )
    (net (code "37") (name "MOSI") (class "Default")
      (node (ref "U$2") (pin "9") (pinfunction "PB1_9") (pintype "bidirectional"))
      (node (ref "U2") (pin "16") (pinfunction "B4_16") (pintype "bidirectional"))
    )
    (net (code "38") (name "MOSI_3V") (class "Default")
      (node (ref "JP1") (pin "2") (pinfunction "2_2") (pintype "passive"))
      (node (ref "U2") (pin "5") (pinfunction "A4_5") (pintype "bidirectional"))
    )
    (net (code "39") (name "MOSI_A") (class "Default")
      (node (ref "ISP") (pin "1") (pinfunction "1_1") (pintype "passive"))
      (node (ref "U$2") (pin "2") (pinfunction "(MOSI_A/TXD)PD3_2") (pintype "bidirectional"))
    )
    (net (code "40") (name "MOTION") (class "Default")
      (node (ref "IC4") (pin "1") (pinfunction "OUT1_1") (pintype "passive"))
      (node (ref "IC4") (pin "5") (pinfunction "OUT2_5") (pintype "passive"))
      (node (ref "P8") (pin "3") (pinfunction "P_3") (pintype "passive"))
      (node (ref "P8") (pin "4") (pinfunction "P_4") (pintype "passive"))
      (node (ref "R15") (pin "1") (pinfunction "1_1") (pintype "passive"))
      (node (ref "R_NULL_4") (pin "1") (pinfunction "1_1") (pintype "passive"))
    )
    (net (code "41") (name "Net-(3V3-PadA)") (class "Default")
      (node (ref "3V3") (pin "A") (pinfunction "A_A") (pintype "passive"))
      (node (ref "R1") (pin "1") (pinfunction "1_1") (pintype "passive"))
    )
    (net (code "42") (name "Net-(5V-PadA)") (class "Default")
      (node (ref "5V") (pin "A") (pinfunction "A_A") (pintype "passive"))
      (node (ref "R18") (pin "1") (pinfunction "1_1") (pintype "passive"))
    )
    (net (code "43") (name "Net-(12V-PadA)") (class "Default")
      (node (ref "12V") (pin "A") (pinfunction "A_A") (pintype "passive"))
      (node (ref "R16") (pin "2") (pinfunction "2_2") (pintype "passive"))
    )
    (net (code "44") (name "Net-(AKKU-PadA)") (class "Default")
      (node (ref "AKKU") (pin "A") (pinfunction "A_A") (pintype "passive"))
      (node (ref "R28") (pin "2") (pinfunction "2_2") (pintype "passive"))
    )
    (net (code "45") (name "Net-(AKT-PadA)") (class "Default")
      (node (ref "AKT") (pin "A") (pinfunction "A_A") (pintype "passive"))
      (node (ref "R17") (pin "2") (pinfunction "2_2") (pintype "passive"))
    )
    (net (code "46") (name "Net-(D1-PadA)") (class "Default")
      (node (ref "D1") (pin "A") (pinfunction "A_A") (pintype "passive"))
      (node (ref "R26") (pin "2") (pinfunction "2_2") (pintype "passive"))
    )
    (net (code "47") (name "Net-(D2-PadA)") (class "Default")
      (node (ref "D2") (pin "A") (pinfunction "A_A") (pintype "passive"))
      (node (ref "R7") (pin "2") (pinfunction "2_2") (pintype "passive"))
    )
    (net (code "48") (name "Net-(D4-C)") (class "Default")
      (node (ref "D4") (pin "3") (pinfunction "C_3") (pintype "passive"))
      (node (ref "R22") (pin "2") (pinfunction "2_2") (pintype "passive"))
      (node (ref "R24") (pin "2") (pinfunction "2_2") (pintype "passive"))
    )
    (net (code "49") (name "Net-(EXT-PadA)") (class "Default")
      (node (ref "EXT") (pin "A") (pinfunction "A_A") (pintype "passive"))
      (node (ref "R25") (pin "2") (pinfunction "2_2") (pintype "passive"))
    )
    (net (code "50") (name "Net-(IC1A--IN)") (class "Default")
      (node (ref "IC1") (pin "2") (pinfunction "-IN_2") (pintype "input"))
      (node (ref "R13") (pin "1") (pinfunction "1_1") (pintype "passive"))
      (node (ref "R21") (pin "2") (pinfunction "2_2") (pintype "passive"))
      (node (ref "R22") (pin "1") (pinfunction "1_1") (pintype "passive"))
    )
    (net (code "51") (name "Net-(IC2-IN)") (class "Default")
      (node (ref "C2") (pin "+") (pinfunction "+_+") (pintype "passive"))
      (node (ref "F1") (pin "2") (pinfunction "2_2") (pintype "passive"))
      (node (ref "IC2") (pin "1") (pinfunction "IN_1") (pintype "input"))
      (node (ref "IC3") (pin "1") (pinfunction "IN_1") (pintype "input"))
    )
    (net (code "52") (name "Net-(IC4-IN)") (class "Default")
      (node (ref "IC4") (pin "2") (pinfunction "IN_2") (pintype "input"))
      (node (ref "VR9") (pin "1") (pinfunction "C_1") (pintype "passive"))
    )
    (net (code "53") (name "Net-(KICK-PadA)") (class "Default")
      (node (ref "KICK") (pin "A") (pinfunction "A_A") (pintype "passive"))
      (node (ref "R23") (pin "2") (pinfunction "2_2") (pintype "passive"))
    )
    (net (code "54") (name "Net-(MOT-PadA)") (class "Default")
      (node (ref "MOT") (pin "A") (pinfunction "A_A") (pintype "passive"))
      (node (ref "R15") (pin "2") (pinfunction "2_2") (pintype "passive"))
    )
    (net (code "55") (name "Net-(Q2-PadG)") (class "Default")
      (node (ref "Q2") (pin "G") (pinfunction "G_G") (pintype "passive"))
      (node (ref "Q3") (pin "G") (pinfunction "G_G") (pintype "passive"))
      (node (ref "Q7") (pin "E") (pinfunction "E_E") (pintype "passive"))
      (node (ref "R34") (pin "2") (pinfunction "2_2") (pintype "passive"))
    )
    (net (code "56") (name "Net-(Q2-PadS)") (class "Default")
      (node (ref "Q2") (pin "S") (pinfunction "S_S") (pintype "passive"))
      (node (ref "Q3") (pin "S") (pinfunction "S_S") (pintype "passive"))
    )
    (net (code "57") (name "Net-(Q4-PadG)") (class "Default")
      (node (ref "Q4") (pin "G") (pinfunction "G_G") (pintype "passive"))
      (node (ref "Q5") (pin "G") (pinfunction "G_G") (pintype "passive"))
      (node (ref "Q6") (pin "E") (pinfunction "E_E") (pintype "passive"))
      (node (ref "R42") (pin "2") (pinfunction "2_2") (pintype "passive"))
    )
    (net (code "58") (name "Net-(Q4-PadS)") (class "Default")
      (node (ref "Q4") (pin "S") (pinfunction "S_S") (pintype "passive"))
      (node (ref "Q5") (pin "S") (pinfunction "S_S") (pintype "passive"))
    )
    (net (code "59") (name "Net-(R6-Pad2)") (class "Default")
      (node (ref "R6") (pin "2") (pinfunction "2_2") (pintype "passive"))
      (node (ref "SJ1") (pin "2") (pinfunction "2_2") (pintype "passive"))
    )
    (net (code "60") (name "Net-(T1-B)") (class "Default")
      (node (ref "R5") (pin "2") (pinfunction "2_2") (pintype "passive"))
      (node (ref "T1") (pin "1") (pinfunction "B_1") (pintype "passive"))
    )
    (net (code "61") (name "Net-(T1-C)") (class "Default")
      (node (ref "D5") (pin "A") (pinfunction "A_A") (pintype "passive"))
      (node (ref "T1") (pin "3") (pinfunction "C_3") (pintype "passive"))
      (node (ref "TDB-05") (pin "-") (pinfunction "2_-") (pintype "passive"))
    )
    (net (code "62") (name "Net-(U$1-RS)") (class "Default")
      (node (ref "R31") (pin "2") (pinfunction "2_2") (pintype "passive"))
      (node (ref "U$1") (pin "8") (pinfunction "RS_8") (pintype "input"))
    )
    (net (code "63") (name "Net-(U$2-AREF)") (class "Default")
      (node (ref "C14") (pin "2") (pinfunction "2_2") (pintype "passive"))
      (node (ref "U$2") (pin "21") (pinfunction "AREF_21") (pintype "bidirectional"))
    )
    (net (code "64") (name "Net-(U$2-PE1(XTAL1))") (class "Default")
      (node (ref "C11") (pin "2") (pinfunction "2_2") (pintype "passive"))
      (node (ref "Q1") (pin "1") (pinfunction "1_1") (pintype "passive"))
      (node (ref "U$2") (pin "10") (pinfunction "PE1(XTAL1)_10") (pintype "bidirectional"))
    )
    (net (code "65") (name "Net-(U$2-PE2(XTAL2))") (class "Default")
      (node (ref "C10") (pin "2") (pinfunction "2_2") (pintype "passive"))
      (node (ref "Q1") (pin "2") (pinfunction "2_2") (pintype "passive"))
      (node (ref "U$2") (pin "11") (pinfunction "PE2(XTAL2)_11") (pintype "bidirectional"))
    )
    (net (code "66") (name "Net-(VR1-C)") (class "Default")
      (node (ref "Q7") (pin "C") (pinfunction "C_C") (pintype "passive"))
      (node (ref "VR1") (pin "1") (pinfunction "C_1") (pintype "passive"))
    )
    (net (code "67") (name "Net-(VR3-C)") (class "Default")
      (node (ref "Q6") (pin "C") (pinfunction "C_C") (pintype "passive"))
      (node (ref "VR3") (pin "1") (pinfunction "C_1") (pintype "passive"))
    )
    (net (code "68") (name "Net-(VR7-C)") (class "Default")
      (node (ref "IC11") (pin "IN") (pinfunction "IN_IN") (pintype "input"))
      (node (ref "VR7") (pin "1") (pinfunction "C_1") (pintype "passive"))
    )
    (net (code "69") (name "Net-(VR8-C)") (class "Default")
      (node (ref "IC12") (pin "IN") (pinfunction "IN_IN") (pintype "input"))
      (node (ref "VR8") (pin "1") (pinfunction "C_1") (pintype "passive"))
    )
    (net (code "70") (name "RST") (class "Default")
      (node (ref "ISP") (pin "5") (pinfunction "5_5") (pintype "passive"))
      (node (ref "U$2") (pin "31") (pinfunction "PE0(RESET)_31") (pintype "input"))
    )
    (net (code "71") (name "RST_ETH") (class "Default")
      (node (ref "U$2") (pin "3") (pinfunction "PC1_3") (pintype "bidirectional"))
      (node (ref "U2") (pin "12") (pinfunction "B8_12") (pintype "bidirectional"))
    )
    (net (code "72") (name "RST_ETH_3V") (class "Default")
      (node (ref "JP2") (pin "3") (pinfunction "3_3") (pintype "passive"))
      (node (ref "U2") (pin "9") (pinfunction "A8_9") (pintype "bidirectional"))
    )
    (net (code "73") (name "RXCAN") (class "Default")
      (node (ref "U$1") (pin "4") (pinfunction "RXD_4") (pintype "output"))
      (node (ref "U$2") (pin "7") (pinfunction "(RXCAN)PC3_7") (pintype "bidirectional"))
    )
    (net (code "74") (name "SCK") (class "Default")
      (node (ref "U$2") (pin "28") (pinfunction "(SCK)PB7_28") (pintype "bidirectional"))
      (node (ref "U2") (pin "15") (pinfunction "B5_15") (pintype "bidirectional"))
    )
    (net (code "75") (name "SCK_3V") (class "Default")
      (node (ref "JP1") (pin "1") (pinfunction "1_1") (pintype "passive"))
      (node (ref "U2") (pin "6") (pinfunction "A5_6") (pintype "bidirectional"))
    )
    (net (code "76") (name "SPEAKER") (class "Default")
      (node (ref "R5") (pin "1") (pinfunction "1_1") (pintype "passive"))
      (node (ref "U$2") (pin "25") (pinfunction "PC7_25") (pintype "bidirectional"))
    )
    (net (code "77") (name "SW_12V") (class "Default")
      (node (ref "D1") (pin "K") (pinfunction "C_K") (pintype "passive"))
      (node (ref "D2") (pin "K") (pinfunction "C_K") (pintype "passive"))
      (node (ref "Q6") (pin "B") (pinfunction "B_B") (pintype "passive"))
      (node (ref "Q7") (pin "B") (pinfunction "B_B") (pintype "passive"))
      (node (ref "SV2") (pin "4") (pinfunction "4_4") (pintype "passive"))
      (node (ref "U$2") (pin "22") (pinfunction "PC6_22") (pintype "bidirectional"))
    )
    (net (code "78") (name "SW_AKT") (class "Default")
      (node (ref "SJ2") (pin "1") (pinfunction "1_1") (pintype "passive"))
      (node (ref "SV2") (pin "6") (pinfunction "6_6") (pintype "passive"))
      (node (ref "U$2") (pin "23") (pinfunction "PB3_23") (pintype "bidirectional"))
      (node (ref "VR7") (pin "3") (pinfunction "A_3") (pintype "passive"))
    )
    (net (code "79") (name "SW_BLAU") (class "Default")
      (node (ref "SV2") (pin "10") (pinfunction "10_10") (pintype "passive"))
      (node (ref "U$2") (pin "15") (pinfunction "PD7_15") (pintype "bidirectional"))
    )
    (net (code "80") (name "SW_KICK") (class "Default")
      (node (ref "SJ2") (pin "2") (pinfunction "2_2") (pintype "passive"))
      (node (ref "VR8") (pin "3") (pinfunction "A_3") (pintype "passive"))
    )
    (net (code "81") (name "SW_MOT") (class "Default")
      (node (ref "SV2") (pin "8") (pinfunction "8_8") (pintype "passive"))
      (node (ref "U$2") (pin "24") (pinfunction "PB4_24") (pintype "bidirectional"))
      (node (ref "VR9") (pin "3") (pinfunction "A_3") (pintype "passive"))
    )
    (net (code "82") (name "TXCAN") (class "Default")
      (node (ref "U$1") (pin "1") (pinfunction "TXD_1") (pintype "input"))
      (node (ref "U$2") (pin "6") (pinfunction "(TXCAN)PC2_6") (pintype "bidirectional"))
    )
    (net (code "83") (name "WOL_ETH") (class "Default")
      (node (ref "U$2") (pin "29") (pinfunction "PD0_29") (pintype "bidirectional"))
      (node (ref "U2") (pin "18") (pinfunction "B2_18") (pintype "bidirectional"))
    )
    (net (code "84") (name "WOL_ETH_3V") (class "Default")
      (node (ref "JP1") (pin "4") (pinfunction "4_4") (pintype "passive"))
      (node (ref "U2") (pin "3") (pinfunction "A2_3") (pintype "bidirectional"))
    )
    (net (code "85") (name "unconnected-(ISP-Pad3)") (class "Default")
      (node (ref "ISP") (pin "3") (pinfunction "3_3") (pintype "passive"))
    )
    (net (code "86") (name "unconnected-(RJ_2-PadP$4)") (class "Default")
      (node (ref "RJ_2") (pin "P$4") (pinfunction "P$4_P$4") (pintype "bidirectional"))
    )
    (net (code "87") (name "unconnected-(U$1-VREF-Pad5)") (class "Default")
      (node (ref "U$1") (pin "5") (pinfunction "VREF_5") (pintype "output"))
    )
  )
)
